# SNES_RGBAmp.net
KiCad netlist of a schematic drawn in EAGLE
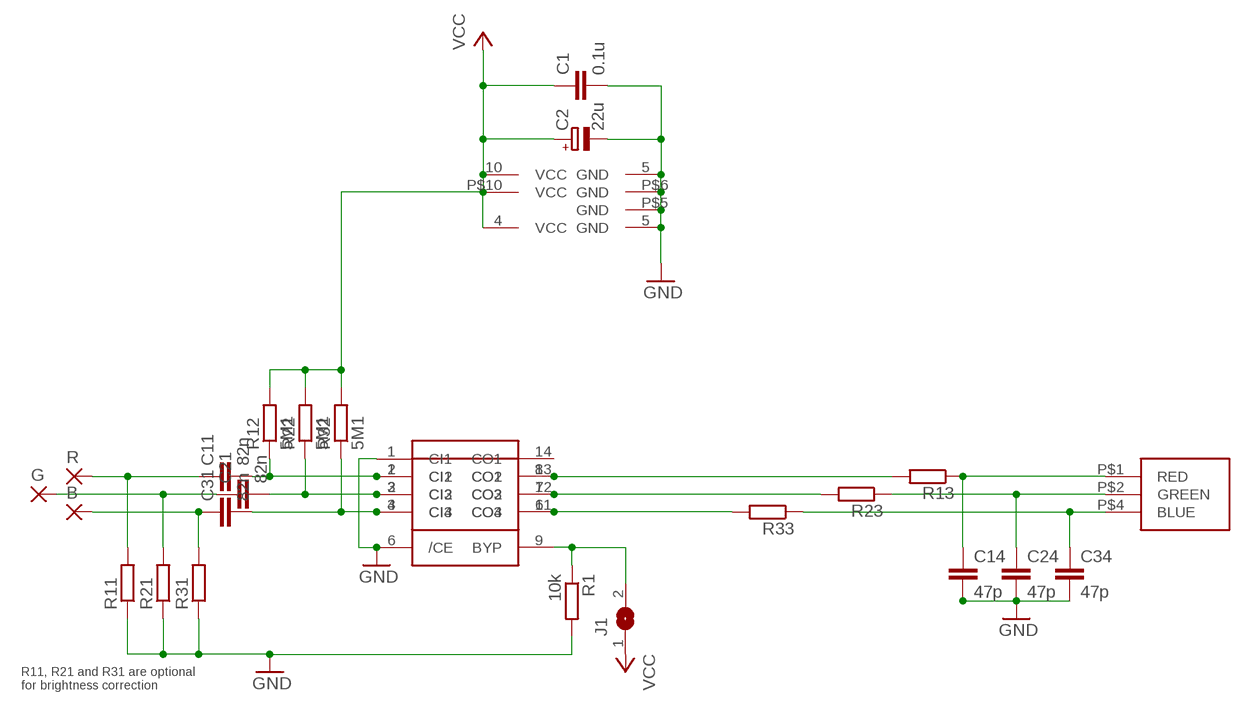
[diagram p0: schematic, sheet 1]

(export (version "E")
  (design (tool "Eeschema 10.0.6"))
  (components
    (comp (ref "B")
      (value "SMD2")
      (footprint "eagle-import:SMD1,27-2,54")
      (libsource (lib "eagle-import") (part "SMD2"))
    )
    (comp (ref "C1")
      (value "0.1u")
      (footprint "eagle-import:C0603K")
      (libsource (lib "eagle-import") (part "C-EUC0603K"))
    )
    (comp (ref "C2")
      (value "22u")
      (footprint "eagle-import:SMC_B")
      (libsource (lib "eagle-import") (part "CPOL-EUSMCB"))
    )
    (comp (ref "C11")
      (value "82n")
      (footprint "eagle-import:C0603K")
      (libsource (lib "eagle-import") (part "C-EUC0603K"))
    )
    (comp (ref "C14")
      (value "47p")
      (footprint "eagle-import:C0603K")
      (libsource (lib "eagle-import") (part "C-EUC0603K"))
    )
    (comp (ref "C21")
      (value "82n")
      (footprint "eagle-import:C0603K")
      (libsource (lib "eagle-import") (part "C-EUC0603K"))
    )
    (comp (ref "C24")
      (value "47p")
      (footprint "eagle-import:C0603K")
      (libsource (lib "eagle-import") (part "C-EUC0603K"))
    )
    (comp (ref "C31")
      (value "82n")
      (footprint "eagle-import:C0603K")
      (libsource (lib "eagle-import") (part "C-EUC0603K"))
    )
    (comp (ref "C34")
      (value "47p")
      (footprint "eagle-import:C0603K")
      (libsource (lib "eagle-import") (part "C-EUC0603K"))
    )
    (comp (ref "G")
      (value "SMD2")
      (footprint "eagle-import:SMD1,27-2,54")
      (libsource (lib "eagle-import") (part "SMD2"))
    )
    (comp (ref "J1") (value "SJ") (footprint "eagle-import:SJ") (libsource (lib "eagle-import") (part "SJ")))
    (comp (ref "R")
      (value "SMD2")
      (footprint "eagle-import:SMD1,27-2,54")
      (libsource (lib "eagle-import") (part "SMD2"))
    )
    (comp (ref "R1")
      (value "10k")
      (footprint "eagle-import:R0603")
      (libsource (lib "eagle-import") (part "R-EU_R0603"))
    )
    (comp (ref "R11")
      (value "R-EU_R0603")
      (footprint "eagle-import:R0603")
      (libsource (lib "eagle-import") (part "R-EU_R0603"))
    )
    (comp (ref "R12")
      (value "5M1")
      (footprint "eagle-import:R0603")
      (libsource (lib "eagle-import") (part "R-EU_R0603"))
    )
    (comp (ref "R13")
      (value "R-EU_R0603")
      (footprint "eagle-import:R0603")
      (libsource (lib "eagle-import") (part "R-EU_R0603"))
    )
    (comp (ref "R21")
      (value "R-EU_R0603")
      (footprint "eagle-import:R0603")
      (libsource (lib "eagle-import") (part "R-EU_R0603"))
    )
    (comp (ref "R22")
      (value "5M1")
      (footprint "eagle-import:R0603")
      (libsource (lib "eagle-import") (part "R-EU_R0603"))
    )
    (comp (ref "R23")
      (value "R-EU_R0603")
      (footprint "eagle-import:R0603")
      (libsource (lib "eagle-import") (part "R-EU_R0603"))
    )
    (comp (ref "R31")
      (value "R-EU_R0603")
      (footprint "eagle-import:R0603")
      (libsource (lib "eagle-import") (part "R-EU_R0603"))
    )
    (comp (ref "R32")
      (value "5M1")
      (footprint "eagle-import:R0603")
      (libsource (lib "eagle-import") (part "R-EU_R0603"))
    )
    (comp (ref "R33")
      (value "R-EU_R0603")
      (footprint "eagle-import:R0603")
      (libsource (lib "eagle-import") (part "R-EU_R0603"))
    )
    (comp (ref "U$1")
      (value "SNES_MULTIAV_RGB_ONLY")
      (footprint "eagle-import:SNES_MULTIAV_RGB_ONLY")
      (libsource (lib "eagle-import") (part "SNES_MULTIAV_RGB_ONLY"))
    )
    (comp (ref "U$2")
      (value "THS7314")
      (footprint "eagle-import:THS7314")
      (libsource (lib "eagle-import") (part "THS7314"))
    )
    (comp (ref "U1")
      (value "THS7374")
      (footprint "eagle-import:THS7374")
      (libsource (lib "eagle-import") (part "THS7374"))
    )
  )
  (nets
    (net (code "1") (name "GND") (class "Default")
      (node (ref "C1") (pin "2") (pinfunction "2_2") (pintype "passive"))
      (node (ref "C14") (pin "2") (pinfunction "2_2") (pintype "passive"))
      (node (ref "C2") (pin "-") (pinfunction "-_-") (pintype "passive"))
      (node (ref "C24") (pin "2") (pinfunction "2_2") (pintype "passive"))
      (node (ref "C34") (pin "2") (pinfunction "2_2") (pintype "passive"))
      (node (ref "R1") (pin "2") (pinfunction "2_2") (pintype "passive"))
      (node (ref "R11") (pin "1") (pinfunction "1_1") (pintype "passive"))
      (node (ref "R21") (pin "1") (pinfunction "1_1") (pintype "passive"))
      (node (ref "R31") (pin "1") (pinfunction "1_1") (pintype "passive"))
      (node (ref "U$1") (pin "P$5") (pinfunction "GND_P$5") (pintype "bidirectional"))
      (node (ref "U$1") (pin "P$6") (pinfunction "GND_P$6") (pintype "bidirectional"))
      (node (ref "U$2") (pin "5") (pinfunction "GND_5") (pintype "bidirectional"))
      (node (ref "U1") (pin "1") (pinfunction "CI1_1") (pintype "bidirectional"))
      (node (ref "U1") (pin "5") (pinfunction "GND_5") (pintype "bidirectional"))
      (node (ref "U1") (pin "6") (pinfunction "/CE_6") (pintype "bidirectional"))
    )
    (net (code "2") (name "Net-(B-P)") (class "Default")
      (node (ref "B") (pin "1") (pinfunction "P_1") (pintype "passive"))
      (node (ref "C31") (pin "1") (pinfunction "1_1") (pintype "passive"))
      (node (ref "R31") (pin "2") (pinfunction "2_2") (pintype "passive"))
    )
    (net (code "3") (name "Net-(G-P)") (class "Default")
      (node (ref "C21") (pin "1") (pinfunction "1_1") (pintype "passive"))
      (node (ref "G") (pin "1") (pinfunction "P_1") (pintype "passive"))
      (node (ref "R21") (pin "2") (pinfunction "2_2") (pintype "passive"))
    )
    (net (code "4") (name "Net-(R-P)") (class "Default")
      (node (ref "C11") (pin "1") (pinfunction "1_1") (pintype "passive"))
      (node (ref "R") (pin "1") (pinfunction "P_1") (pintype "passive"))
      (node (ref "R11") (pin "2") (pinfunction "2_2") (pintype "passive"))
    )
    (net (code "5") (name "Net-(U$1C-BLUE)") (class "Default")
      (node (ref "C34") (pin "1") (pinfunction "1_1") (pintype "passive"))
      (node (ref "R33") (pin "1") (pinfunction "1_1") (pintype "passive"))
      (node (ref "U$1") (pin "P$4") (pinfunction "BLUE_P$4") (pintype "bidirectional"))
    )
    (net (code "6") (name "Net-(U$1C-GREEN)") (class "Default")
      (node (ref "C24") (pin "1") (pinfunction "1_1") (pintype "passive"))
      (node (ref "R23") (pin "1") (pinfunction "1_1") (pintype "passive"))
      (node (ref "U$1") (pin "P$2") (pinfunction "GREEN_P$2") (pintype "bidirectional"))
    )
    (net (code "7") (name "Net-(U$1C-RED)") (class "Default")
      (node (ref "C14") (pin "1") (pinfunction "1_1") (pintype "passive"))
      (node (ref "R13") (pin "1") (pinfunction "1_1") (pintype "passive"))
      (node (ref "U$1") (pin "P$1") (pinfunction "RED_P$1") (pintype "bidirectional"))
    )
    (net (code "8") (name "Net-(U$2A-CI1)") (class "Default")
      (node (ref "C11") (pin "2") (pinfunction "2_2") (pintype "passive"))
      (node (ref "R12") (pin "1") (pinfunction "1_1") (pintype "passive"))
      (node (ref "U$2") (pin "1") (pinfunction "CI1_1") (pintype "bidirectional"))
      (node (ref "U1") (pin "2") (pinfunction "CI2_2") (pintype "bidirectional"))
    )
    (net (code "9") (name "Net-(U$2A-CI2)") (class "Default")
      (node (ref "C21") (pin "2") (pinfunction "2_2") (pintype "passive"))
      (node (ref "R22") (pin "1") (pinfunction "1_1") (pintype "passive"))
      (node (ref "U$2") (pin "2") (pinfunction "CI2_2") (pintype "bidirectional"))
      (node (ref "U1") (pin "3") (pinfunction "CI3_3") (pintype "bidirectional"))
    )
    (net (code "10") (name "Net-(U$2A-CI3)") (class "Default")
      (node (ref "C31") (pin "2") (pinfunction "2_2") (pintype "passive"))
      (node (ref "R32") (pin "1") (pinfunction "1_1") (pintype "passive"))
      (node (ref "U$2") (pin "3") (pinfunction "CI3_3") (pintype "bidirectional"))
      (node (ref "U1") (pin "4") (pinfunction "CI4_4") (pintype "bidirectional"))
    )
    (net (code "11") (name "Net-(U$2A-CO1)") (class "Default")
      (node (ref "R13") (pin "2") (pinfunction "2_2") (pintype "passive"))
      (node (ref "U$2") (pin "8") (pinfunction "CO1_8") (pintype "bidirectional"))
      (node (ref "U1") (pin "13") (pinfunction "CO2_13") (pintype "bidirectional"))
    )
    (net (code "12") (name "Net-(U$2A-CO2)") (class "Default")
      (node (ref "R23") (pin "2") (pinfunction "2_2") (pintype "passive"))
      (node (ref "U$2") (pin "7") (pinfunction "CO2_7") (pintype "bidirectional"))
      (node (ref "U1") (pin "12") (pinfunction "CO3_12") (pintype "bidirectional"))
    )
    (net (code "13") (name "Net-(U$2A-CO3)") (class "Default")
      (node (ref "R33") (pin "2") (pinfunction "2_2") (pintype "passive"))
      (node (ref "U$2") (pin "6") (pinfunction "CO3_6") (pintype "bidirectional"))
      (node (ref "U1") (pin "11") (pinfunction "CO4_11") (pintype "bidirectional"))
    )
    (net (code "14") (name "Net-(U1A-BYP)") (class "Default")
      (node (ref "J1") (pin "2") (pinfunction "2_2") (pintype "passive"))
      (node (ref "R1") (pin "1") (pinfunction "1_1") (pintype "passive"))
      (node (ref "U1") (pin "9") (pinfunction "BYP_9") (pintype "bidirectional"))
    )
    (net (code "15") (name "VCC") (class "Default")
      (node (ref "C1") (pin "1") (pinfunction "1_1") (pintype "passive"))
      (node (ref "C2") (pin "+") (pinfunction "+_+") (pintype "passive"))
      (node (ref "J1") (pin "1") (pinfunction "1_1") (pintype "passive"))
      (node (ref "R12") (pin "2") (pinfunction "2_2") (pintype "passive"))
      (node (ref "R22") (pin "2") (pinfunction "2_2") (pintype "passive"))
      (node (ref "R32") (pin "2") (pinfunction "2_2") (pintype "passive"))
      (node (ref "U$1") (pin "P$10") (pinfunction "VCC_P$10") (pintype "bidirectional"))
      (node (ref "U$2") (pin "4") (pinfunction "VCC_4") (pintype "bidirectional"))
      (node (ref "U1") (pin "10") (pinfunction "VCC_10") (pintype "bidirectional"))
    )
    (net (code "16") (name "unconnected-(U1A-CO1-Pad14)") (class "Default")
      (node (ref "U1") (pin "14") (pinfunction "CO1_14") (pintype "bidirectional"))
    )
  )
)
